# Supercaps25F.net
KiCad netlist of a schematic drawn in EAGLE
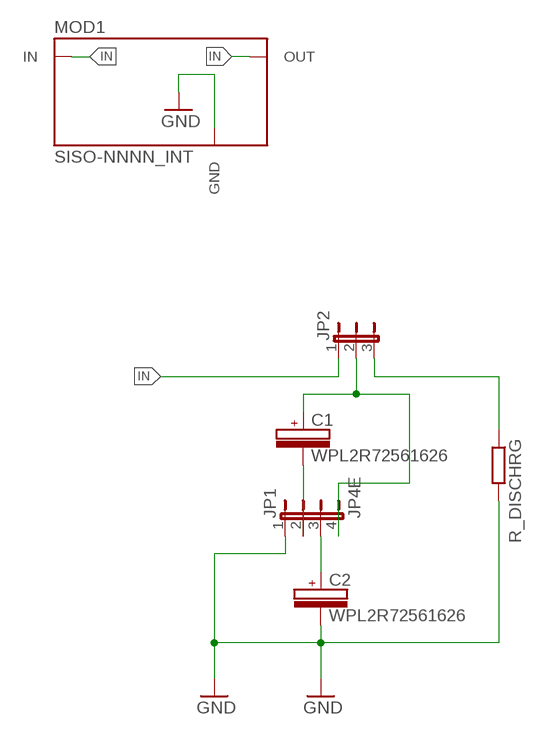
[diagram p0: schematic, sheet 1]

(export (version "E")
  (design (tool "Eeschema 10.0.6"))
  (components
    (comp (ref "C1")
      (value "WPL2R72561626")
      (footprint "eagle-import:DLC_16X26")
      (libsource (lib "eagle-import") (part "WPL2R72561626"))
    )
    (comp (ref "C2")
      (value "WPL2R72561626")
      (footprint "eagle-import:DLC_16X26")
      (libsource (lib "eagle-import") (part "WPL2R72561626"))
    )
    (comp (ref "JP1")
      (value "JP4E")
      (footprint "eagle-import:JP4")
      (libsource (lib "eagle-import") (part "JP4E"))
    )
    (comp (ref "JP2")
      (value "JP2E")
      (footprint "eagle-import:JP2")
      (libsource (lib "eagle-import") (part "JP2E"))
    )
    (comp (ref "MOD1")
      (value "SISO-NNNN_INT")
      (footprint "eagle-import:SISO-NNNN")
      (libsource (lib "eagle-import") (part "SISO-NNNN_INT"))
    )
    (comp (ref "R_DISCHRG")
      (value "R_THROUGH-HOLE")
      (footprint "eagle-import:R_THROUGH-HOLE")
      (libsource (lib "eagle-import") (part "R_THROUGH-HOLE"))
    )
  )
  (nets
    (net (code "1") (name "GND") (class "Default")
      (node (ref "C2") (pin "2") (pinfunction "2_2") (pintype "passive"))
      (node (ref "JP1") (pin "1") (pinfunction "1_1") (pintype "passive"))
      (node (ref "MOD1") (pin "GND1") (pinfunction "GND_GND1") (pintype "power_in"))
      (node (ref "MOD1") (pin "GND2") (pinfunction "GND_GND2") (pintype "power_in"))
      (node (ref "MOD1") (pin "GND3") (pinfunction "GND_GND3") (pintype "power_in"))
      (node (ref "MOD1") (pin "GND4") (pinfunction "GND_GND4") (pintype "power_in"))
      (node (ref "R_DISCHRG") (pin "2") (pinfunction "2_2") (pintype "passive"))
    )
    (net (code "2") (name "IN") (class "Default")
      (node (ref "JP2") (pin "1") (pinfunction "1_1") (pintype "passive"))
      (node (ref "MOD1") (pin "IN1") (pinfunction "IN_IN1") (pintype "input"))
      (node (ref "MOD1") (pin "IN2") (pinfunction "IN_IN2") (pintype "input"))
      (node (ref "MOD1") (pin "IN3") (pinfunction "IN_IN3") (pintype "input"))
      (node (ref "MOD1") (pin "IN4") (pinfunction "IN_IN4") (pintype "input"))
      (node (ref "MOD1") (pin "OUT1") (pinfunction "OUT_OUT1") (pintype "output"))
      (node (ref "MOD1") (pin "OUT2") (pinfunction "OUT_OUT2") (pintype "output"))
      (node (ref "MOD1") (pin "OUT3") (pinfunction "OUT_OUT3") (pintype "output"))
      (node (ref "MOD1") (pin "OUT4") (pinfunction "OUT_OUT4") (pintype "output"))
    )
    (net (code "3") (name "Net-(C1-Pad1)") (class "Default")
      (node (ref "C1") (pin "1") (pinfunction "1_1") (pintype "passive"))
      (node (ref "JP1") (pin "4") (pinfunction "4_4") (pintype "passive"))
      (node (ref "JP2") (pin "2") (pinfunction "2_2") (pintype "passive"))
    )
    (net (code "4") (name "Net-(C1-Pad2)") (class "Default")
      (node (ref "C1") (pin "2") (pinfunction "2_2") (pintype "passive"))
      (node (ref "JP1") (pin "2") (pinfunction "2_2") (pintype "passive"))
    )
    (net (code "5") (name "Net-(C2-Pad1)") (class "Default")
      (node (ref "C2") (pin "1") (pinfunction "1_1") (pintype "passive"))
      (node (ref "JP1") (pin "3") (pinfunction "3_3") (pintype "passive"))
    )
    (net (code "6") (name "Net-(JP2-Pad3)") (class "Default")
      (node (ref "JP2") (pin "3") (pinfunction "3_3") (pintype "passive"))
      (node (ref "R_DISCHRG") (pin "1") (pinfunction "1_1") (pintype "passive"))
    )
  )
)
